# Peripherals.net
KiCad netlist of a schematic drawn in Altium Designer
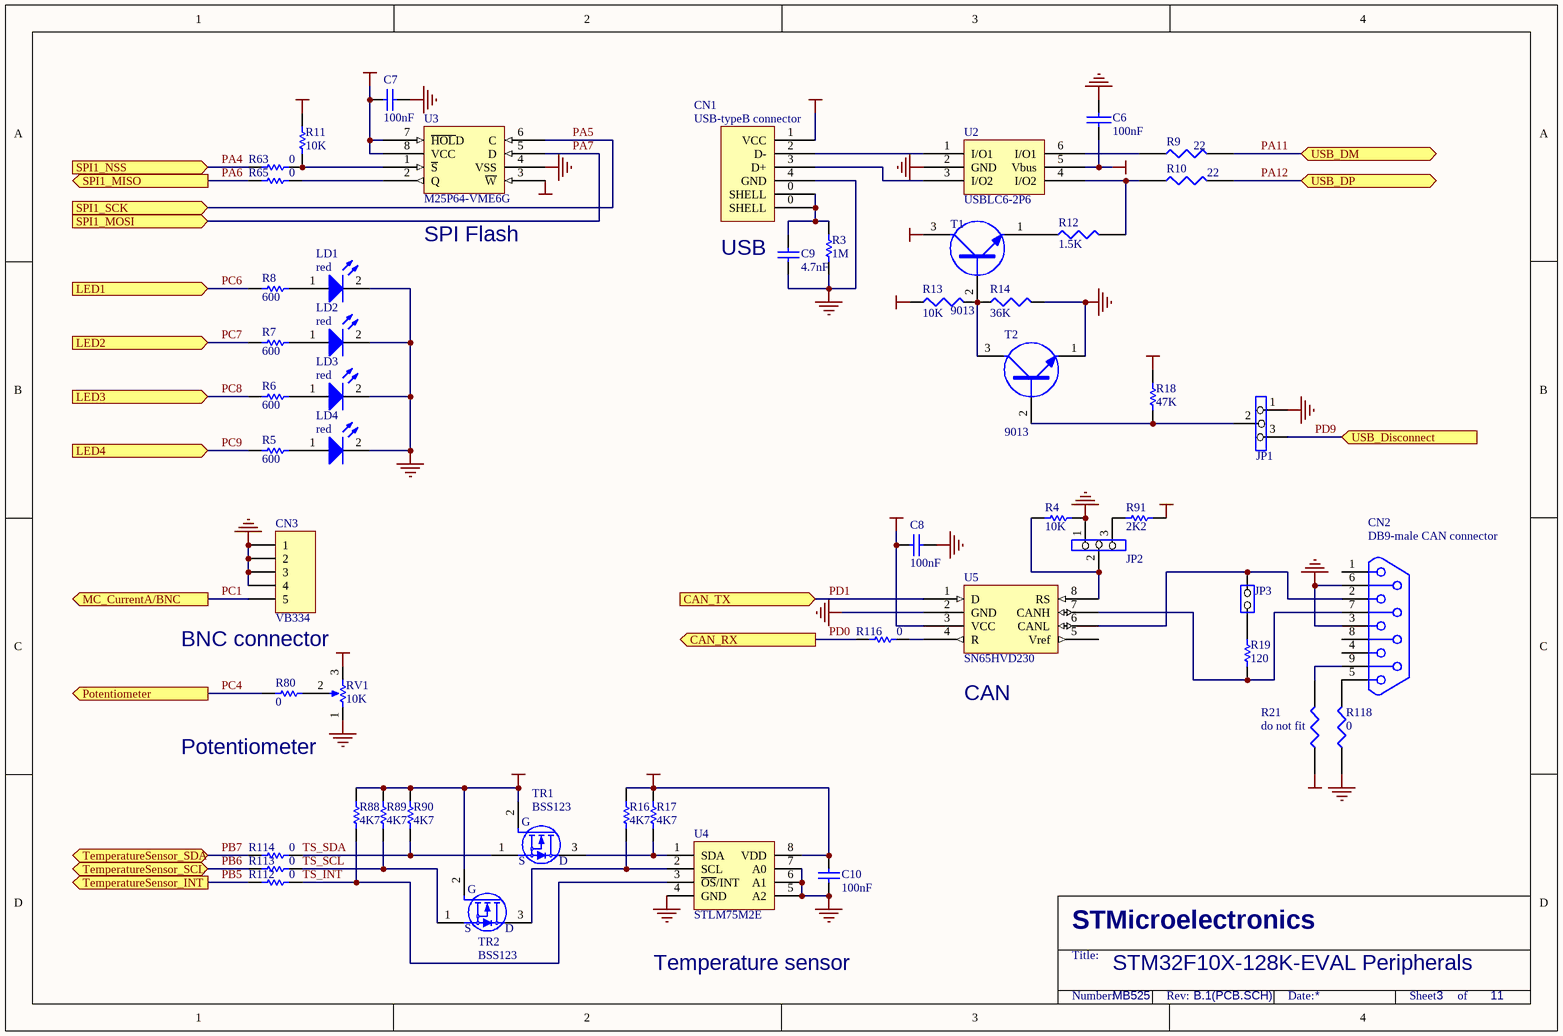
[diagram p0: Peripherals.SchDoc]

(export (version "E")
  (design (tool "Eeschema 10.0.6"))
  (components
    (comp (ref "C6")
      (value "100nF")
      (footprint "0603P")
      (description "Capacitor")
      (libsource (lib "*") (part "CAP"))
    )
    (comp (ref "C7")
      (value "100nF")
      (footprint "0603P")
      (description "Capacitor")
      (fields (field (name "PUBLISHER") "Altium Limited"))
      (libsource (lib "Miscellaneous Devices") (part "CAP"))
    )
    (comp (ref "C8")
      (value "100nF")
      (footprint "0603P")
      (description "Capacitor")
      (fields (field (name "PUBLISHER") "Altium Limited"))
      (libsource (lib "Miscellaneous Devices") (part "CAP"))
    )
    (comp (ref "C9")
      (value "4.7nF")
      (description "Capacitor")
      (fields (field (name "PUBLISHER") "Altium Limited"))
      (libsource (lib "Miscellaneous Devices") (part "CAP"))
    )
    (comp (ref "C10")
      (value "100nF")
      (footprint "0603P")
      (description "Capacitor")
      (fields (field (name "PUBLISHER") "Altium Limited"))
      (libsource (lib "Miscellaneous Devices") (part "cap"))
    )
    (comp (ref "CN1")
      (value "USB-typeB connector")
      (footprint "USB-B")
      (description "USB-B")
      (libsource (lib "Documents") (part "USB-B"))
    )
    (comp (ref "CN2") (value "DB9-male CAN connector") (footprint "DB9/M") (libsource (lib "*") (part "DB9")))
    (comp (ref "CN3")
      (value "VB334")
      (footprint "VB334")
      (description "Header, 5-Pin")
      (fields (field (name "PUBLISHER") "Altium Limited"))
      (libsource (lib "Miscellaneous Connectors") (part "Header 5"))
    )
    (comp (ref "JP1") (value "~") (footprint "SIP3") (libsource (lib "STR910_SCHLIB") (part "Jumper3")))
    (comp (ref "JP2") (value "~") (footprint "SIP3") (libsource (lib "STR910_SCHLIB") (part "Jumper3")))
    (comp (ref "JP3") (value "~") (footprint "SIP2") (libsource (lib "*") (part "JP2")))
    (comp (ref "LD1")
      (value "red")
      (footprint "D0603")
      (description "Typical RED, GREEN, YELLOW, AMBER GaAs LED")
      (fields (field (name "PUBLISHER") "Altium Limited"))
      (libsource (lib "Miscellaneous Devices") (part "LED2"))
    )
    (comp (ref "LD2")
      (value "red")
      (footprint "D0603")
      (description "Typical RED, GREEN, YELLOW, AMBER GaAs LED")
      (fields (field (name "PUBLISHER") "Altium Limited"))
      (libsource (lib "Miscellaneous Devices") (part "LED2"))
    )
    (comp (ref "LD3")
      (value "red")
      (footprint "D0603")
      (description "Typical RED, GREEN, YELLOW, AMBER GaAs LED")
      (fields (field (name "PUBLISHER") "Altium Limited"))
      (libsource (lib "Miscellaneous Devices") (part "LED2"))
    )
    (comp (ref "LD4")
      (value "red")
      (footprint "D0603")
      (description "Typical RED, GREEN, YELLOW, AMBER GaAs LED")
      (fields (field (name "PUBLISHER") "Altium Limited"))
      (libsource (lib "Miscellaneous Devices") (part "LED2"))
    )
    (comp (ref "R3")
      (value "1M")
      (description "Resistor")
      (fields (field (name "PUBLISHER") "Altium Limited"))
      (libsource (lib "Miscellaneous Devices") (part "Res1"))
    )
    (comp (ref "R4")
      (value "10K")
      (description "Resistor")
      (fields (field (name "PUBLISHER") "Altium Limited"))
      (libsource (lib "Miscellaneous Devices") (part "res1"))
    )
    (comp (ref "R5")
      (value "600")
      (description "Resistor")
      (fields (field (name "PUBLISHER") "Altium Limited"))
      (libsource (lib "Miscellaneous Devices") (part "Res1"))
    )
    (comp (ref "R6")
      (value "600")
      (description "Resistor")
      (fields (field (name "PUBLISHER") "Altium Limited"))
      (libsource (lib "Miscellaneous Devices") (part "Res1"))
    )
    (comp (ref "R7")
      (value "600")
      (description "Resistor")
      (fields (field (name "PUBLISHER") "Altium Limited"))
      (libsource (lib "Miscellaneous Devices") (part "Res1"))
    )
    (comp (ref "R8")
      (value "600")
      (description "Resistor")
      (fields (field (name "PUBLISHER") "Altium Limited"))
      (libsource (lib "Miscellaneous Devices") (part "Res1"))
    )
    (comp (ref "R9") (value "22") (footprint "0603") (libsource (lib "*") (part "RES1")))
    (comp (ref "R10") (value "22") (footprint "0603") (libsource (lib "*") (part "RES1")))
    (comp (ref "R11")
      (value "10K")
      (description "Resistor")
      (fields (field (name "PUBLISHER") "Altium Limited"))
      (libsource (lib "Miscellaneous Devices") (part "Res1"))
    )
    (comp (ref "R12") (value "1.5K") (footprint "0603") (libsource (lib "*") (part "RES1")))
    (comp (ref "R13") (value "10K") (footprint "0603") (libsource (lib "*") (part "R")))
    (comp (ref "R14") (value "36K") (footprint "0603") (libsource (lib "*") (part "R")))
    (comp (ref "R16")
      (value "4K7")
      (description "Resistor")
      (fields (field (name "PUBLISHER") "Altium Limited"))
      (libsource (lib "Miscellaneous Devices") (part "Res1"))
    )
    (comp (ref "R17")
      (value "4K7")
      (description "Resistor")
      (fields (field (name "PUBLISHER") "Altium Limited"))
      (libsource (lib "Miscellaneous Devices") (part "Res1"))
    )
    (comp (ref "R18")
      (value "47K")
      (description "Resistor")
      (fields (field (name "PUBLISHER") "Altium Limited"))
      (libsource (lib "Miscellaneous Devices") (part "Res1"))
    )
    (comp (ref "R19")
      (value "120")
      (description "Resistor")
      (fields (field (name "PUBLISHER") "Altium Limited"))
      (libsource (lib "Miscellaneous Devices") (part "res1"))
    )
    (comp (ref "R21") (value "do not fit") (footprint "0603") (libsource (lib "") (part "RES1_1")))
    (comp (ref "R63")
      (value "0")
      (description "Resistor")
      (fields (field (name "PUBLISHER") "Altium Limited"))
      (libsource (lib "Miscellaneous Devices") (part "Res1"))
    )
    (comp (ref "R65")
      (value "0")
      (description "Resistor")
      (fields (field (name "PUBLISHER") "Altium Limited"))
      (libsource (lib "Miscellaneous Devices") (part "Res1"))
    )
    (comp (ref "R80")
      (value "0")
      (description "Resistor")
      (fields (field (name "PUBLISHER") "Altium Limited"))
      (libsource (lib "Miscellaneous Devices") (part "Res1"))
    )
    (comp (ref "R88")
      (value "4K7")
      (description "Resistor")
      (fields (field (name "PUBLISHER") "Altium Limited"))
      (libsource (lib "Miscellaneous Devices") (part "Res1"))
    )
    (comp (ref "R89")
      (value "4K7")
      (description "Resistor")
      (fields (field (name "PUBLISHER") "Altium Limited"))
      (libsource (lib "Miscellaneous Devices") (part "Res1"))
    )
    (comp (ref "R90")
      (value "4K7")
      (description "Resistor")
      (fields (field (name "PUBLISHER") "Altium Limited"))
      (libsource (lib "Miscellaneous Devices") (part "Res1"))
    )
    (comp (ref "R91")
      (value "2K2")
      (description "Resistor")
      (fields (field (name "PUBLISHER") "Altium Limited"))
      (libsource (lib "Miscellaneous Devices") (part "res1"))
    )
    (comp (ref "R112")
      (value "0")
      (description "Resistor")
      (fields (field (name "PUBLISHER") "Altium Limited"))
      (libsource (lib "Miscellaneous Devices") (part "Res1"))
    )
    (comp (ref "R113")
      (value "0")
      (description "Resistor")
      (fields (field (name "PUBLISHER") "Altium Limited"))
      (libsource (lib "Miscellaneous Devices") (part "Res1"))
    )
    (comp (ref "R114")
      (value "0")
      (description "Resistor")
      (fields (field (name "PUBLISHER") "Altium Limited"))
      (libsource (lib "Miscellaneous Devices") (part "Res1"))
    )
    (comp (ref "R116")
      (value "0")
      (description "Resistor")
      (fields (field (name "PUBLISHER") "Altium Limited"))
      (libsource (lib "Miscellaneous Devices") (part "Res1"))
    )
    (comp (ref "R118") (value "0") (footprint "0603") (libsource (lib "") (part "RES1_1")))
    (comp (ref "RV1") (value "10K") (footprint "ADJRH") (libsource (lib "STR910_SCHLIB") (part "RV")))
    (comp (ref "T1") (value "9013") (footprint "SOT-23") (libsource (lib "*") (part "NPN")))
    (comp (ref "T2") (value "9013") (footprint "SOT-23") (libsource (lib "*") (part "NPN")))
    (comp (ref "TR1") (value "BSS123") (footprint "SOT-23") (libsource (lib "MB525") (part "2N7000")))
    (comp (ref "TR2") (value "BSS123") (footprint "SOT-23") (libsource (lib "MB525") (part "2N7000")))
    (comp (ref "U2")
      (value "USBLC6-2P6")
      (footprint "SOT-666")
      (libsource (lib "STR910_SCHLIB") (part "USBLC6-2"))
    )
    (comp (ref "U3")
      (value "M25P64-VME6G")
      (footprint "VDFPN8(8*6)")
      (libsource (lib "STR910_SCHLIB") (part "M25P64-VME6G"))
    )
    (comp (ref "U4") (value "STLM75M2E") (footprint "SO8") (libsource (lib "MB525") (part "STLM75DW2F")))
    (comp (ref "U5")
      (value "SN65HVD230")
      (footprint "SO8")
      (libsource (lib "STR910_SCHLIB") (part "SN65HVD230D"))
    )
  )
  (nets
    (net (code "1") (name "+3V3") (class "Default")
      (node (ref "C7") (pin "2") (pinfunction "2_2") (pintype "passive"))
      (node (ref "C8") (pin "2") (pinfunction "2_2") (pintype "passive"))
      (node (ref "R11") (pin "2") (pinfunction "2_2") (pintype "passive"))
      (node (ref "R18") (pin "2") (pinfunction "2_2") (pintype "passive"))
      (node (ref "R21") (pin "1") (pinfunction "1_1") (pintype "passive"))
      (node (ref "R88") (pin "2") (pinfunction "2_2") (pintype "passive"))
      (node (ref "R89") (pin "2") (pinfunction "2_2") (pintype "passive"))
      (node (ref "R90") (pin "2") (pinfunction "2_2") (pintype "passive"))
      (node (ref "R91") (pin "2") (pinfunction "2_2") (pintype "passive"))
      (node (ref "RV1") (pin "3") (pinfunction "TOP_3") (pintype "passive"))
      (node (ref "T1") (pin "3") (pinfunction "C_3") (pintype "passive"))
      (node (ref "TR1") (pin "2") (pinfunction "G_2") (pintype "passive"))
      (node (ref "TR2") (pin "2") (pinfunction "G_2") (pintype "passive"))
      (node (ref "U3") (pin "3") (pinfunction "~{W}_3") (pintype "input"))
      (node (ref "U3") (pin "7") (pinfunction "~{HOL}D_7") (pintype "input"))
      (node (ref "U3") (pin "8") (pinfunction "VCC_8") (pintype "power_in"))
      (node (ref "U5") (pin "3") (pinfunction "VCC_3") (pintype "power_in"))
    )
    (net (code "2") (name "+5V") (class "Default")
      (node (ref "C10") (pin "2") (pinfunction "2_2") (pintype "passive"))
      (node (ref "R16") (pin "2") (pinfunction "2_2") (pintype "passive"))
      (node (ref "R17") (pin "2") (pinfunction "2_2") (pintype "passive"))
      (node (ref "U4") (pin "8") (pinfunction "VDD_8") (pintype "passive"))
    )
    (net (code "3") (name "/PA4") (class "Default")
      (node (ref "R63") (pin "2") (pinfunction "2_2") (pintype "passive"))
    )
    (net (code "4") (name "/PA5") (class "Default")
      (node (ref "U3") (pin "6") (pinfunction "C_6") (pintype "input"))
    )
    (net (code "5") (name "/PA6") (class "Default")
      (node (ref "R65") (pin "1") (pinfunction "1_1") (pintype "passive"))
    )
    (net (code "6") (name "/PA7") (class "Default")
      (node (ref "U3") (pin "5") (pinfunction "D_5") (pintype "input"))
    )
    (net (code "7") (name "/PA11") (class "Default")
      (node (ref "R9") (pin "2") (pinfunction "2_2") (pintype "passive"))
    )
    (net (code "8") (name "/PA12") (class "Default")
      (node (ref "R10") (pin "2") (pinfunction "2_2") (pintype "passive"))
    )
    (net (code "9") (name "/PB5") (class "Default")
      (node (ref "R112") (pin "2") (pinfunction "2_2") (pintype "passive"))
    )
    (net (code "10") (name "/PB6") (class "Default")
      (node (ref "R113") (pin "2") (pinfunction "2_2") (pintype "passive"))
    )
    (net (code "11") (name "/PB7") (class "Default")
      (node (ref "R114") (pin "2") (pinfunction "2_2") (pintype "passive"))
    )
    (net (code "12") (name "/PC1") (class "Default")
      (node (ref "CN3") (pin "5") (pinfunction "5_5") (pintype "passive"))
    )
    (net (code "13") (name "/PC4") (class "Default")
      (node (ref "R80") (pin "1") (pinfunction "1_1") (pintype "passive"))
    )
    (net (code "14") (name "/PC6") (class "Default")
      (node (ref "R8") (pin "2") (pinfunction "2_2") (pintype "passive"))
    )
    (net (code "15") (name "/PC7") (class "Default")
      (node (ref "R7") (pin "2") (pinfunction "2_2") (pintype "passive"))
    )
    (net (code "16") (name "/PC8") (class "Default")
      (node (ref "R6") (pin "2") (pinfunction "2_2") (pintype "passive"))
    )
    (net (code "17") (name "/PC9") (class "Default")
      (node (ref "R5") (pin "2") (pinfunction "2_2") (pintype "passive"))
    )
    (net (code "18") (name "/PD0") (class "Default")
      (node (ref "R116") (pin "2") (pinfunction "2_2") (pintype "passive"))
    )
    (net (code "19") (name "/PD1") (class "Default")
      (node (ref "U5") (pin "1") (pinfunction "D_1") (pintype "input"))
    )
    (net (code "20") (name "/PD9") (class "Default") (node (ref "JP1") (pin "3") (pintype "passive")))
    (net (code "21") (name "/TS_INT") (class "Default")
      (node (ref "R112") (pin "1") (pinfunction "1_1") (pintype "passive"))
      (node (ref "R88") (pin "1") (pinfunction "1_1") (pintype "passive"))
      (node (ref "U4") (pin "3") (pinfunction "~{OS}/INT_3") (pintype "passive"))
    )
    (net (code "22") (name "/TS_SCL") (class "Default")
      (node (ref "R113") (pin "1") (pinfunction "1_1") (pintype "passive"))
      (node (ref "R89") (pin "1") (pinfunction "1_1") (pintype "passive"))
      (node (ref "TR2") (pin "1") (pinfunction "S_1") (pintype "passive"))
    )
    (net (code "23") (name "/TS_SDA") (class "Default")
      (node (ref "R114") (pin "1") (pinfunction "1_1") (pintype "passive"))
      (node (ref "R90") (pin "1") (pinfunction "1_1") (pintype "passive"))
      (node (ref "TR1") (pin "1") (pinfunction "S_1") (pintype "passive"))
    )
    (net (code "24") (name "GND") (class "Default")
      (node (ref "C10") (pin "1") (pinfunction "1_1") (pintype "passive"))
      (node (ref "C6") (pin "1") (pinfunction "1_1") (pintype "passive"))
      (node (ref "C7") (pin "1") (pinfunction "1_1") (pintype "passive"))
      (node (ref "C8") (pin "1") (pinfunction "1_1") (pintype "passive"))
      (node (ref "C9") (pin "1") (pinfunction "1_1") (pintype "passive"))
      (node (ref "CN1") (pin "4") (pinfunction "GND_4") (pintype "passive"))
      (node (ref "CN2") (pin "3") (pinfunction "3_3") (pintype "passive"))
      (node (ref "CN2") (pin "6") (pinfunction "6_6") (pintype "passive"))
      (node (ref "CN3") (pin "1") (pinfunction "1_1") (pintype "passive"))
      (node (ref "CN3") (pin "2") (pinfunction "2_2") (pintype "passive"))
      (node (ref "CN3") (pin "3") (pinfunction "3_3") (pintype "passive"))
      (node (ref "CN3") (pin "4") (pinfunction "4_4") (pintype "passive"))
      (node (ref "JP1") (pin "1") (pintype "passive"))
      (node (ref "JP2") (pin "1") (pintype "passive"))
      (node (ref "LD1") (pin "2") (pinfunction "K_2") (pintype "passive"))
      (node (ref "LD2") (pin "2") (pinfunction "K_2") (pintype "passive"))
      (node (ref "LD3") (pin "2") (pinfunction "K_2") (pintype "passive"))
      (node (ref "LD4") (pin "2") (pinfunction "K_2") (pintype "passive"))
      (node (ref "R118") (pin "1") (pinfunction "1_1") (pintype "passive"))
      (node (ref "R14") (pin "2") (pinfunction "2_2") (pintype "passive"))
      (node (ref "R3") (pin "1") (pinfunction "1_1") (pintype "passive"))
      (node (ref "R4") (pin "2") (pinfunction "2_2") (pintype "passive"))
      (node (ref "RV1") (pin "1") (pinfunction "BOT_1") (pintype "passive"))
      (node (ref "T2") (pin "1") (pinfunction "E_1") (pintype "passive"))
      (node (ref "U2") (pin "2") (pinfunction "GND_2") (pintype "passive"))
      (node (ref "U3") (pin "4") (pinfunction "VSS_4") (pintype "power_in"))
      (node (ref "U4") (pin "4") (pinfunction "GND_4") (pintype "passive"))
      (node (ref "U4") (pin "5") (pinfunction "A2_5") (pintype "passive"))
      (node (ref "U4") (pin "6") (pinfunction "A1_6") (pintype "passive"))
      (node (ref "U4") (pin "7") (pinfunction "A0_7") (pintype "passive"))
      (node (ref "U5") (pin "2") (pinfunction "GND_2") (pintype "power_in"))
    )
    (net (code "25") (name "Net-(CN1-D+)") (class "Default")
      (node (ref "CN1") (pin "3") (pinfunction "D+_3") (pintype "passive"))
      (node (ref "U2") (pin "3") (pinfunction "I/O2_3") (pintype "passive"))
    )
    (net (code "26") (name "Net-(CN1-D-)") (class "Default")
      (node (ref "CN1") (pin "2") (pinfunction "D-_2") (pintype "passive"))
      (node (ref "U2") (pin "1") (pinfunction "I/O1_1") (pintype "passive"))
    )
    (net (code "27") (name "Net-(CN1-SHELL)") (class "Default")
      (node (ref "C9") (pin "2") (pinfunction "2_2") (pintype "passive"))
      (node (ref "CN1") (pin "0") (pinfunction "SHELL_0") (pintype "passive"))
      (node (ref "R3") (pin "2") (pinfunction "2_2") (pintype "passive"))
    )
    (net (code "28") (name "Net-(CN2-Pad5)") (class "Default")
      (node (ref "CN2") (pin "5") (pinfunction "5_5") (pintype "passive"))
      (node (ref "R118") (pin "2") (pinfunction "2_2") (pintype "passive"))
    )
    (net (code "29") (name "Net-(CN2-Pad9)") (class "Default")
      (node (ref "CN2") (pin "9") (pinfunction "9_9") (pintype "passive"))
      (node (ref "R21") (pin "2") (pinfunction "2_2") (pintype "passive"))
    )
    (net (code "30") (name "Net-(JP2-Pad3)") (class "Default")
      (node (ref "JP2") (pin "3") (pintype "passive"))
      (node (ref "R91") (pin "1") (pinfunction "1_1") (pintype "passive"))
    )
    (net (code "31") (name "Net-(JP3-COMMON)") (class "Default")
      (node (ref "JP3") (pin "1") (pinfunction "COMMON_1") (pintype "passive"))
      (node (ref "R19") (pin "2") (pinfunction "2_2") (pintype "passive"))
    )
    (net (code "32") (name "Net-(JP3-NO)") (class "Default")
      (node (ref "CN2") (pin "2") (pinfunction "2_2") (pintype "passive"))
      (node (ref "JP3") (pin "2") (pinfunction "NO_2") (pintype "passive"))
      (node (ref "U5") (pin "6") (pinfunction "CANL_6") (pintype "bidirectional"))
    )
    (net (code "33") (name "Net-(LD1-A)") (class "Default")
      (node (ref "LD1") (pin "1") (pinfunction "A_1") (pintype "passive"))
      (node (ref "R8") (pin "1") (pinfunction "1_1") (pintype "passive"))
    )
    (net (code "34") (name "Net-(LD2-A)") (class "Default")
      (node (ref "LD2") (pin "1") (pinfunction "A_1") (pintype "passive"))
      (node (ref "R7") (pin "1") (pinfunction "1_1") (pintype "passive"))
    )
    (net (code "35") (name "Net-(LD3-A)") (class "Default")
      (node (ref "LD3") (pin "1") (pinfunction "A_1") (pintype "passive"))
      (node (ref "R6") (pin "1") (pinfunction "1_1") (pintype "passive"))
    )
    (net (code "36") (name "Net-(LD4-A)") (class "Default")
      (node (ref "LD4") (pin "1") (pinfunction "A_1") (pintype "passive"))
      (node (ref "R5") (pin "1") (pinfunction "1_1") (pintype "passive"))
    )
    (net (code "37") (name "Net-(R9-Pad1)") (class "Default")
      (node (ref "R9") (pin "1") (pinfunction "1_1") (pintype "passive"))
      (node (ref "U2") (pin "6") (pinfunction "I/O1_6") (pintype "passive"))
    )
    (net (code "38") (name "Net-(R10-Pad1)") (class "Default")
      (node (ref "R10") (pin "1") (pinfunction "1_1") (pintype "passive"))
      (node (ref "R12") (pin "2") (pinfunction "2_2") (pintype "passive"))
      (node (ref "U2") (pin "4") (pinfunction "I/O2_4") (pintype "passive"))
    )
    (net (code "39") (name "Net-(RV1-TAP)") (class "Default")
      (node (ref "R80") (pin "2") (pinfunction "2_2") (pintype "passive"))
      (node (ref "RV1") (pin "2") (pinfunction "TAP_2") (pintype "passive"))
    )
    (net (code "40") (name "Net-(T1-B)") (class "Default")
      (node (ref "R13") (pin "2") (pinfunction "2_2") (pintype "passive"))
      (node (ref "R14") (pin "1") (pinfunction "1_1") (pintype "passive"))
      (node (ref "T1") (pin "2") (pinfunction "B_2") (pintype "passive"))
      (node (ref "T2") (pin "3") (pinfunction "C_3") (pintype "passive"))
    )
    (net (code "41") (name "Net-(T1-E)") (class "Default")
      (node (ref "R12") (pin "1") (pinfunction "1_1") (pintype "passive"))
      (node (ref "T1") (pin "1") (pinfunction "E_1") (pintype "passive"))
    )
    (net (code "42") (name "Net-(T2-B)") (class "Default")
      (node (ref "JP1") (pin "2") (pintype "passive"))
      (node (ref "R18") (pin "1") (pinfunction "1_1") (pintype "passive"))
      (node (ref "T2") (pin "2") (pinfunction "B_2") (pintype "passive"))
    )
    (net (code "43") (name "Net-(TR1-D)") (class "Default")
      (node (ref "R17") (pin "1") (pinfunction "1_1") (pintype "passive"))
      (node (ref "TR1") (pin "3") (pinfunction "D_3") (pintype "passive"))
      (node (ref "U4") (pin "1") (pinfunction "SDA_1") (pintype "passive"))
    )
    (net (code "44") (name "Net-(TR2-D)") (class "Default")
      (node (ref "R16") (pin "1") (pinfunction "1_1") (pintype "passive"))
      (node (ref "TR2") (pin "3") (pinfunction "D_3") (pintype "passive"))
      (node (ref "U4") (pin "2") (pinfunction "SCL_2") (pintype "passive"))
    )
    (net (code "45") (name "Net-(U3-Q)") (class "Default")
      (node (ref "R65") (pin "2") (pinfunction "2_2") (pintype "passive"))
      (node (ref "U3") (pin "2") (pinfunction "Q_2") (pintype "output"))
    )
    (net (code "46") (name "Net-(U3-~{S})") (class "Default")
      (node (ref "R11") (pin "1") (pinfunction "1_1") (pintype "passive"))
      (node (ref "R63") (pin "1") (pinfunction "1_1") (pintype "passive"))
      (node (ref "U3") (pin "1") (pinfunction "~{S}_1") (pintype "input"))
    )
    (net (code "47") (name "Net-(U5-CANH)") (class "Default")
      (node (ref "CN2") (pin "7") (pinfunction "7_7") (pintype "passive"))
      (node (ref "R19") (pin "1") (pinfunction "1_1") (pintype "passive"))
      (node (ref "U5") (pin "7") (pinfunction "CANH_7") (pintype "bidirectional"))
    )
    (net (code "48") (name "Net-(U5-R)") (class "Default")
      (node (ref "R116") (pin "1") (pinfunction "1_1") (pintype "passive"))
      (node (ref "U5") (pin "4") (pinfunction "R_4") (pintype "output"))
    )
    (net (code "49") (name "Net-(U5-RS)") (class "Default")
      (node (ref "JP2") (pin "2") (pintype "passive"))
      (node (ref "R4") (pin "1") (pinfunction "1_1") (pintype "passive"))
      (node (ref "U5") (pin "8") (pinfunction "RS_8") (pintype "input"))
    )
    (net (code "50") (name "U5V") (class "Default")
      (node (ref "C6") (pin "2") (pinfunction "2_2") (pintype "passive"))
      (node (ref "CN1") (pin "1") (pinfunction "VCC_1") (pintype "passive"))
      (node (ref "R13") (pin "1") (pinfunction "1_1") (pintype "passive"))
      (node (ref "U2") (pin "5") (pinfunction "Vbus_5") (pintype "passive"))
    )
    (net (code "51") (name "unconnected-(CN2-Pad1)") (class "Default")
      (node (ref "CN2") (pin "1") (pinfunction "1_1") (pintype "passive"))
    )
    (net (code "52") (name "unconnected-(CN2-Pad4)") (class "Default")
      (node (ref "CN2") (pin "4") (pinfunction "4_4") (pintype "passive"))
    )
    (net (code "53") (name "unconnected-(CN2-Pad8)") (class "Default")
      (node (ref "CN2") (pin "8") (pinfunction "8_8") (pintype "passive"))
    )
    (net (code "54") (name "unconnected-(U5-Vref-Pad5)") (class "Default")
      (node (ref "U5") (pin "5") (pinfunction "Vref_5") (pintype "output"))
    )
  )
)
